# Lumiboard_-_main_board_rev_B.net
KiCad netlist of a schematic drawn in EAGLE
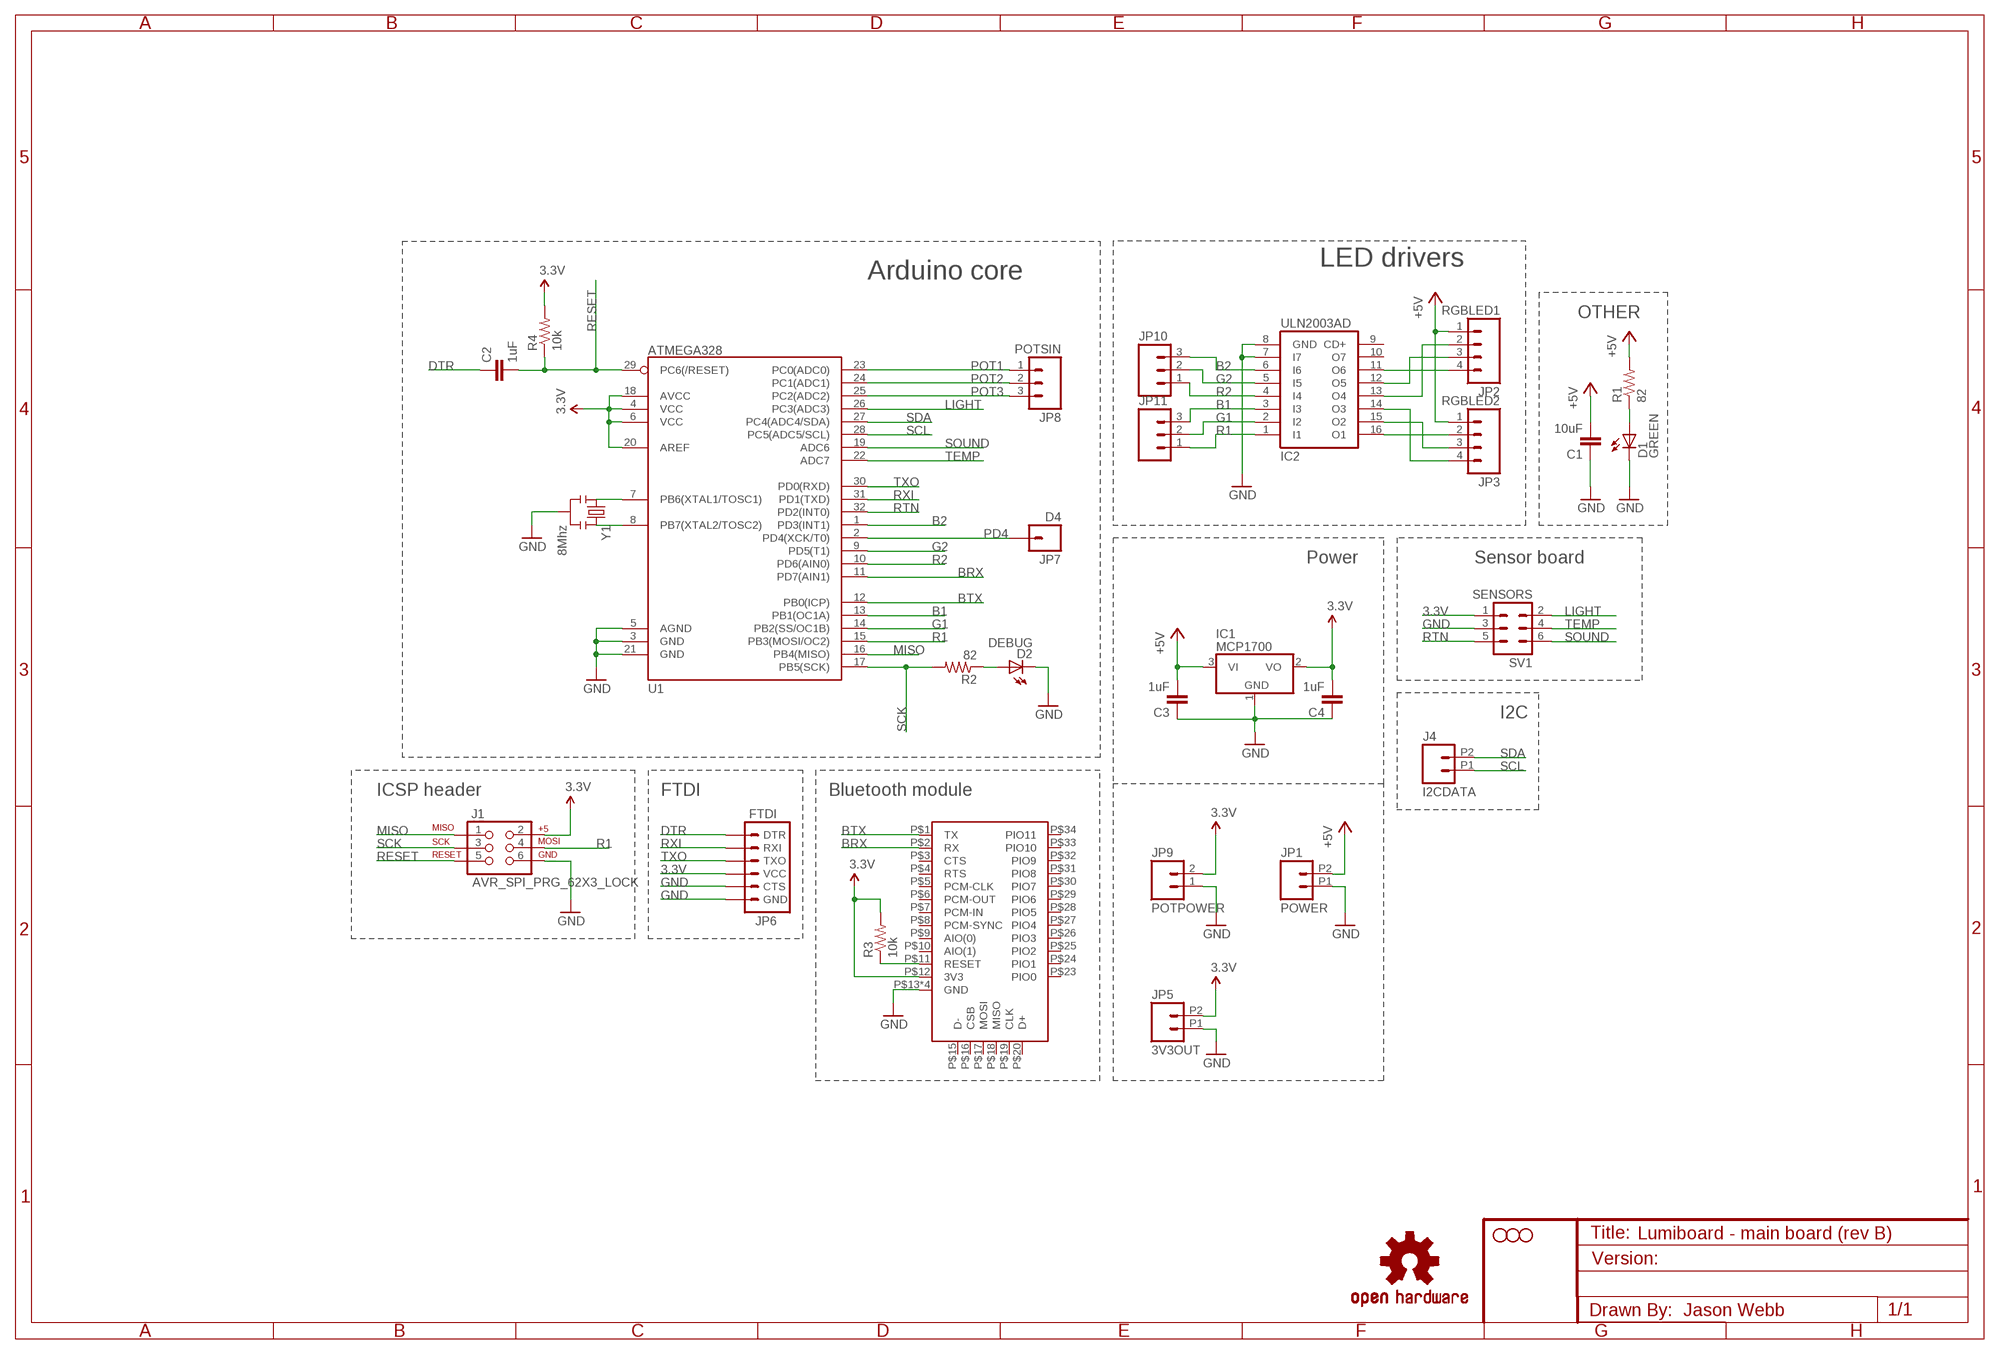
[diagram p0: schematic, sheet 1]

(export (version "E")
  (design (tool "Eeschema 10.0.6"))
  (components
    (comp (ref "C1")
      (value "10uF")
      (footprint "eagle-import:0805")
      (libsource (lib "eagle-import") (part "CAP0805"))
    )
    (comp (ref "C2")
      (value "1uF")
      (footprint "eagle-import:0805")
      (libsource (lib "eagle-import") (part "CAP0805"))
    )
    (comp (ref "C3")
      (value "1uF")
      (footprint "eagle-import:0805")
      (libsource (lib "eagle-import") (part "CAP0805"))
    )
    (comp (ref "C4")
      (value "1uF")
      (footprint "eagle-import:0805")
      (libsource (lib "eagle-import") (part "CAP0805"))
    )
    (comp (ref "D1")
      (value "GREEN")
      (footprint "eagle-import:CHIPLED_0805")
      (libsource (lib "eagle-import") (part "LEDCHIPLED_0805"))
    )
    (comp (ref "D2")
      (value "DEBUG")
      (footprint "eagle-import:CHIPLED_0805")
      (libsource (lib "eagle-import") (part "LEDCHIPLED_0805"))
    )
    (comp (ref "H1")
      (value "STAND-OFFTIGHT")
      (footprint "eagle-import:STAND-OFF-TIGHT")
      (libsource (lib "eagle-import") (part "STAND-OFFTIGHT"))
    )
    (comp (ref "H2")
      (value "STAND-OFFTIGHT")
      (footprint "eagle-import:STAND-OFF-TIGHT")
      (libsource (lib "eagle-import") (part "STAND-OFFTIGHT"))
    )
    (comp (ref "H3")
      (value "STAND-OFFTIGHT")
      (footprint "eagle-import:STAND-OFF-TIGHT")
      (libsource (lib "eagle-import") (part "STAND-OFFTIGHT"))
    )
    (comp (ref "IC1")
      (value "MCP1700")
      (footprint "eagle-import:SOT23")
      (libsource (lib "eagle-import") (part "MCP1703CB"))
    )
    (comp (ref "IC2")
      (value "ULN2003AD")
      (footprint "eagle-import:SO16")
      (libsource (lib "eagle-import") (part "ULN2003AD"))
    )
    (comp (ref "J1")
      (value "AVR_SPI_PRG_62X3_LOCK")
      (footprint "eagle-import:2X3_LOCK")
      (libsource (lib "eagle-import") (part "AVR_SPI_PRG_62X3_LOCK"))
    )
    (comp (ref "J4")
      (value "I2CDATA")
      (footprint "eagle-import:1X02_2.54_SCREWTERM")
      (libsource (lib "eagle-import") (part "M022.54MM_SCREWTERM"))
    )
    (comp (ref "JP1")
      (value "POWER")
      (footprint "eagle-import:1X02_2.54_SCREWTERM")
      (libsource (lib "eagle-import") (part "M022.54MM_SCREWTERM"))
    )
    (comp (ref "JP2")
      (value "RGBLED1")
      (footprint "eagle-import:1X04")
      (libsource (lib "eagle-import") (part "M04PTH"))
    )
    (comp (ref "JP3")
      (value "RGBLED2")
      (footprint "eagle-import:1X04")
      (libsource (lib "eagle-import") (part "M04PTH"))
    )
    (comp (ref "JP5")
      (value "3V3OUT")
      (footprint "eagle-import:1X02_2.54_SCREWTERM")
      (libsource (lib "eagle-import") (part "M022.54MM_SCREWTERM"))
    )
    (comp (ref "JP6")
      (value "FTDI")
      (footprint "eagle-import:1X06_LOCK")
      (libsource (lib "eagle-import") (part "ARDUINO_SERIAL_PROGRAMLOCK"))
    )
    (comp (ref "JP7")
      (value "D4")
      (footprint "eagle-import:1X01")
      (libsource (lib "eagle-import") (part "M01PTH"))
    )
    (comp (ref "JP8")
      (value "POTSIN")
      (footprint "eagle-import:1X03")
      (libsource (lib "eagle-import") (part "M03PTH"))
    )
    (comp (ref "JP9")
      (value "POTPOWER")
      (footprint "eagle-import:1X02")
      (libsource (lib "eagle-import") (part "M02PTH"))
    )
    (comp (ref "JP10")
      (value "M03PTH")
      (footprint "eagle-import:1X03")
      (libsource (lib "eagle-import") (part "SparkFun-Connectors_M03PTH"))
    )
    (comp (ref "JP11")
      (value "M03PTH")
      (footprint "eagle-import:1X03")
      (libsource (lib "eagle-import") (part "SparkFun-Connectors_M03PTH"))
    )
    (comp (ref "LOGO1")
      (value "OSHW-LOGOL")
      (footprint "eagle-import:OSHW-LOGO-L")
      (libsource (lib "eagle-import") (part "OSHW-LOGOL"))
    )
    (comp (ref "R1")
      (value "82")
      (footprint "eagle-import:R0805")
      (libsource (lib "eagle-import") (part "R-US_R0805"))
    )
    (comp (ref "R2")
      (value "82")
      (footprint "eagle-import:R0805")
      (libsource (lib "eagle-import") (part "R-US_R0805"))
    )
    (comp (ref "R3")
      (value "10k")
      (footprint "eagle-import:R0805")
      (libsource (lib "eagle-import") (part "R-US_R0805"))
    )
    (comp (ref "R4")
      (value "10k")
      (footprint "eagle-import:R0805")
      (libsource (lib "eagle-import") (part "R-US_R0805"))
    )
    (comp (ref "SV1")
      (value "SENSORS")
      (footprint "eagle-import:ML6")
      (libsource (lib "eagle-import") (part "ML6"))
    )
    (comp (ref "U1")
      (value "ATMEGA328")
      (footprint "eagle-import:TQFP32-08")
      (libsource (lib "eagle-import") (part "ATMEGA168"))
    )
    (comp (ref "U2")
      (value "DX_BT_MODULE")
      (footprint "eagle-import:DXBLUETOOTHMODULE")
      (libsource (lib "eagle-import") (part "DX_BT_MODULE"))
    )
    (comp (ref "Y1")
      (value "8Mhz")
      (footprint "eagle-import:RESONATOR-SMD")
      (libsource (lib "eagle-import") (part "RESONATORSMD"))
    )
  )
  (nets
    (net (code "1") (name "+5V") (class "Default")
      (node (ref "C1") (pin "2") (pinfunction "2_2") (pintype "passive"))
      (node (ref "C3") (pin "2") (pinfunction "2_2") (pintype "passive"))
      (node (ref "IC1") (pin "3") (pinfunction "VI_3") (pintype "input"))
      (node (ref "JP1") (pin "P2") (pinfunction "2_P2") (pintype "passive"))
      (node (ref "JP2") (pin "1") (pinfunction "1_1") (pintype "passive"))
      (node (ref "JP3") (pin "1") (pinfunction "1_1") (pintype "passive"))
      (node (ref "R1") (pin "2") (pinfunction "2_2") (pintype "passive"))
    )
    (net (code "2") (name "/B1") (class "Default")
      (node (ref "IC2") (pin "3") (pinfunction "I3_3") (pintype "input"))
      (node (ref "JP11") (pin "3") (pinfunction "3_3") (pintype "passive"))
      (node (ref "U1") (pin "13") (pinfunction "PB1(OC1A)_13") (pintype "bidirectional"))
    )
    (net (code "3") (name "/B2") (class "Default")
      (node (ref "IC2") (pin "6") (pinfunction "I6_6") (pintype "input"))
      (node (ref "JP10") (pin "3") (pinfunction "3_3") (pintype "passive"))
      (node (ref "U1") (pin "1") (pinfunction "PD3(INT1)_1") (pintype "bidirectional"))
    )
    (net (code "4") (name "/BRX") (class "Default")
      (node (ref "U1") (pin "11") (pinfunction "PD7(AIN1)_11") (pintype "bidirectional"))
      (node (ref "U2") (pin "P$2") (pinfunction "RX_P$2") (pintype "input"))
    )
    (net (code "5") (name "/BTX") (class "Default")
      (node (ref "U1") (pin "12") (pinfunction "PB0(ICP)_12") (pintype "bidirectional"))
      (node (ref "U2") (pin "P$1") (pinfunction "TX_P$1") (pintype "output"))
    )
    (net (code "6") (name "/DTR") (class "Default")
      (node (ref "C2") (pin "1") (pinfunction "1_1") (pintype "passive"))
      (node (ref "JP6") (pin "1") (pinfunction "DTR_1") (pintype "passive"))
    )
    (net (code "7") (name "/G1") (class "Default")
      (node (ref "IC2") (pin "2") (pinfunction "I2_2") (pintype "input"))
      (node (ref "JP11") (pin "2") (pinfunction "2_2") (pintype "passive"))
      (node (ref "U1") (pin "14") (pinfunction "PB2(SS/OC1B)_14") (pintype "bidirectional"))
    )
    (net (code "8") (name "/G2") (class "Default")
      (node (ref "IC2") (pin "5") (pinfunction "I5_5") (pintype "input"))
      (node (ref "JP10") (pin "2") (pinfunction "2_2") (pintype "passive"))
      (node (ref "U1") (pin "9") (pinfunction "PD5(T1)_9") (pintype "bidirectional"))
    )
    (net (code "9") (name "/LIGHT") (class "Default")
      (node (ref "SV1") (pin "2") (pinfunction "2_2") (pintype "passive"))
      (node (ref "U1") (pin "26") (pinfunction "PC3(ADC3)_26") (pintype "bidirectional"))
    )
    (net (code "10") (name "/MISO") (class "Default")
      (node (ref "J1") (pin "1") (pinfunction "1_1") (pintype "passive"))
      (node (ref "U1") (pin "16") (pinfunction "PB4(MISO)_16") (pintype "bidirectional"))
    )
    (net (code "11") (name "/PD4") (class "Default")
      (node (ref "JP7") (pin "1") (pinfunction "1_1") (pintype "passive"))
      (node (ref "U1") (pin "2") (pinfunction "PD4(XCK/T0)_2") (pintype "bidirectional"))
    )
    (net (code "12") (name "/POT1") (class "Default")
      (node (ref "JP8") (pin "1") (pinfunction "1_1") (pintype "passive"))
      (node (ref "U1") (pin "23") (pinfunction "PC0(ADC0)_23") (pintype "bidirectional"))
    )
    (net (code "13") (name "/POT2") (class "Default")
      (node (ref "JP8") (pin "2") (pinfunction "2_2") (pintype "passive"))
      (node (ref "U1") (pin "24") (pinfunction "PC1(ADC1)_24") (pintype "bidirectional"))
    )
    (net (code "14") (name "/POT3") (class "Default")
      (node (ref "JP8") (pin "3") (pinfunction "3_3") (pintype "passive"))
      (node (ref "U1") (pin "25") (pinfunction "PC2(ADC2)_25") (pintype "bidirectional"))
    )
    (net (code "15") (name "/R1") (class "Default")
      (node (ref "IC2") (pin "1") (pinfunction "I1_1") (pintype "input"))
      (node (ref "J1") (pin "4") (pinfunction "4_4") (pintype "passive"))
      (node (ref "JP11") (pin "1") (pinfunction "1_1") (pintype "passive"))
      (node (ref "U1") (pin "15") (pinfunction "PB3(MOSI/OC2)_15") (pintype "bidirectional"))
    )
    (net (code "16") (name "/R2") (class "Default")
      (node (ref "IC2") (pin "4") (pinfunction "I4_4") (pintype "input"))
      (node (ref "JP10") (pin "1") (pinfunction "1_1") (pintype "passive"))
      (node (ref "U1") (pin "10") (pinfunction "PD6(AIN0)_10") (pintype "bidirectional"))
    )
    (net (code "17") (name "/RESET") (class "Default")
      (node (ref "C2") (pin "2") (pinfunction "2_2") (pintype "passive"))
      (node (ref "J1") (pin "5") (pinfunction "5_5") (pintype "passive"))
      (node (ref "R4") (pin "1") (pinfunction "1_1") (pintype "passive"))
      (node (ref "U1") (pin "29") (pinfunction "PC6(/RESET)_29") (pintype "bidirectional"))
    )
    (net (code "18") (name "/RTN") (class "Default")
      (node (ref "SV1") (pin "5") (pinfunction "5_5") (pintype "passive"))
      (node (ref "U1") (pin "32") (pinfunction "PD2(INT0)_32") (pintype "bidirectional"))
    )
    (net (code "19") (name "/RXI") (class "Default")
      (node (ref "JP6") (pin "2") (pinfunction "RXI_2") (pintype "passive"))
      (node (ref "U1") (pin "31") (pinfunction "PD1(TXD)_31") (pintype "bidirectional"))
    )
    (net (code "20") (name "/SCK") (class "Default")
      (node (ref "J1") (pin "3") (pinfunction "3_3") (pintype "passive"))
      (node (ref "R2") (pin "2") (pinfunction "2_2") (pintype "passive"))
      (node (ref "U1") (pin "17") (pinfunction "PB5(SCK)_17") (pintype "bidirectional"))
    )
    (net (code "21") (name "/SCL") (class "Default")
      (node (ref "J4") (pin "P1") (pinfunction "1_P1") (pintype "passive"))
      (node (ref "U1") (pin "28") (pinfunction "PC5(ADC5/SCL)_28") (pintype "bidirectional"))
    )
    (net (code "22") (name "/SDA") (class "Default")
      (node (ref "J4") (pin "P2") (pinfunction "2_P2") (pintype "passive"))
      (node (ref "U1") (pin "27") (pinfunction "PC4(ADC4/SDA)_27") (pintype "bidirectional"))
    )
    (net (code "23") (name "/SOUND") (class "Default")
      (node (ref "SV1") (pin "6") (pinfunction "6_6") (pintype "passive"))
      (node (ref "U1") (pin "19") (pinfunction "ADC6_19") (pintype "bidirectional"))
    )
    (net (code "24") (name "/TEMP") (class "Default")
      (node (ref "SV1") (pin "4") (pinfunction "4_4") (pintype "passive"))
      (node (ref "U1") (pin "22") (pinfunction "ADC7_22") (pintype "bidirectional"))
    )
    (net (code "25") (name "/TXO") (class "Default")
      (node (ref "JP6") (pin "3") (pinfunction "TXO_3") (pintype "passive"))
      (node (ref "U1") (pin "30") (pinfunction "PD0(RXD)_30") (pintype "bidirectional"))
    )
    (net (code "26") (name "3.3V") (class "Default")
      (node (ref "C4") (pin "2") (pinfunction "2_2") (pintype "passive"))
      (node (ref "IC1") (pin "2") (pinfunction "VO_2") (pintype "passive"))
      (node (ref "J1") (pin "2") (pinfunction "2_2") (pintype "passive"))
      (node (ref "JP5") (pin "P2") (pinfunction "2_P2") (pintype "passive"))
      (node (ref "JP6") (pin "4") (pinfunction "VCC_4") (pintype "passive"))
      (node (ref "JP9") (pin "2") (pinfunction "2_2") (pintype "passive"))
      (node (ref "R3") (pin "2") (pinfunction "2_2") (pintype "passive"))
      (node (ref "R4") (pin "2") (pinfunction "2_2") (pintype "passive"))
      (node (ref "SV1") (pin "1") (pinfunction "1_1") (pintype "passive"))
      (node (ref "U1") (pin "18") (pinfunction "AVCC_18") (pintype "bidirectional"))
      (node (ref "U1") (pin "20") (pinfunction "AREF_20") (pintype "bidirectional"))
      (node (ref "U1") (pin "4") (pinfunction "VCC_4") (pintype "bidirectional"))
      (node (ref "U1") (pin "6") (pinfunction "VCC_6") (pintype "bidirectional"))
      (node (ref "U2") (pin "P$12") (pinfunction "3V3_P$12") (pintype "power_in"))
    )
    (net (code "27") (name "GND") (class "Default")
      (node (ref "C1") (pin "1") (pinfunction "1_1") (pintype "passive"))
      (node (ref "C3") (pin "1") (pinfunction "1_1") (pintype "passive"))
      (node (ref "C4") (pin "1") (pinfunction "1_1") (pintype "passive"))
      (node (ref "D1") (pin "C") (pinfunction "C_C") (pintype "passive"))
      (node (ref "D2") (pin "C") (pinfunction "C_C") (pintype "passive"))
      (node (ref "IC1") (pin "1") (pinfunction "GND_1") (pintype "passive"))
      (node (ref "IC2") (pin "7") (pinfunction "I7_7") (pintype "input"))
      (node (ref "IC2") (pin "8") (pinfunction "GND_8") (pintype "power_in"))
      (node (ref "J1") (pin "6") (pinfunction "6_6") (pintype "passive"))
      (node (ref "JP1") (pin "P1") (pinfunction "1_P1") (pintype "passive"))
      (node (ref "JP5") (pin "P1") (pinfunction "1_P1") (pintype "passive"))
      (node (ref "JP6") (pin "5") (pinfunction "CTS_5") (pintype "passive"))
      (node (ref "JP6") (pin "6") (pinfunction "GND_6") (pintype "passive"))
      (node (ref "JP9") (pin "1") (pinfunction "1_1") (pintype "passive"))
      (node (ref "SV1") (pin "3") (pinfunction "3_3") (pintype "passive"))
      (node (ref "U1") (pin "21") (pinfunction "GND_21") (pintype "bidirectional"))
      (node (ref "U1") (pin "3") (pinfunction "GND_3") (pintype "bidirectional"))
      (node (ref "U1") (pin "5") (pinfunction "AGND_5") (pintype "bidirectional"))
      (node (ref "U2") (pin "P$13") (pinfunction "GND_P$13") (pintype "power_in"))
      (node (ref "U2") (pin "P$14") (pinfunction "GND_P$14") (pintype "power_in"))
      (node (ref "U2") (pin "P$21") (pinfunction "GND_P$21") (pintype "power_in"))
      (node (ref "U2") (pin "P$22") (pinfunction "GND_P$22") (pintype "power_in"))
      (node (ref "Y1") (pin "2") (pinfunction "2_2") (pintype "passive"))
    )
    (net (code "28") (name "Net-(D1-PadA)") (class "Default")
      (node (ref "D1") (pin "A") (pinfunction "A_A") (pintype "passive"))
      (node (ref "R1") (pin "1") (pinfunction "1_1") (pintype "passive"))
    )
    (net (code "29") (name "Net-(D2-PadA)") (class "Default")
      (node (ref "D2") (pin "A") (pinfunction "A_A") (pintype "passive"))
      (node (ref "R2") (pin "1") (pinfunction "1_1") (pintype "passive"))
    )
    (net (code "30") (name "Net-(IC2-O1)") (class "Default")
      (node (ref "IC2") (pin "16") (pinfunction "O1_16") (pintype "open_collector"))
      (node (ref "JP3") (pin "2") (pinfunction "2_2") (pintype "passive"))
    )
    (net (code "31") (name "Net-(IC2-O2)") (class "Default")
      (node (ref "IC2") (pin "15") (pinfunction "O2_15") (pintype "open_collector"))
      (node (ref "JP3") (pin "3") (pinfunction "3_3") (pintype "passive"))
    )
    (net (code "32") (name "Net-(IC2-O3)") (class "Default")
      (node (ref "IC2") (pin "14") (pinfunction "O3_14") (pintype "open_collector"))
      (node (ref "JP3") (pin "4") (pinfunction "4_4") (pintype "passive"))
    )
    (net (code "33") (name "Net-(IC2-O4)") (class "Default")
      (node (ref "IC2") (pin "13") (pinfunction "O4_13") (pintype "open_collector"))
      (node (ref "JP2") (pin "2") (pinfunction "2_2") (pintype "passive"))
    )
    (net (code "34") (name "Net-(IC2-O5)") (class "Default")
      (node (ref "IC2") (pin "12") (pinfunction "O5_12") (pintype "open_collector"))
      (node (ref "JP2") (pin "3") (pinfunction "3_3") (pintype "passive"))
    )
    (net (code "35") (name "Net-(IC2-O6)") (class "Default")
      (node (ref "IC2") (pin "11") (pinfunction "O6_11") (pintype "open_collector"))
      (node (ref "JP2") (pin "4") (pinfunction "4_4") (pintype "passive"))
    )
    (net (code "36") (name "Net-(U1-PB6(XTAL1{slash}TOSC1))") (class "Default")
      (node (ref "U1") (pin "7") (pinfunction "PB6(XTAL1/TOSC1)_7") (pintype "bidirectional"))
      (node (ref "Y1") (pin "1") (pinfunction "1_1") (pintype "passive"))
    )
    (net (code "37") (name "Net-(U1-PB7(XTAL2{slash}TOSC2))") (class "Default")
      (node (ref "U1") (pin "8") (pinfunction "PB7(XTAL2/TOSC2)_8") (pintype "bidirectional"))
      (node (ref "Y1") (pin "3") (pinfunction "3_3") (pintype "passive"))
    )
    (net (code "38") (name "Net-(U2-RESET)") (class "Default")
      (node (ref "R3") (pin "1") (pinfunction "1_1") (pintype "passive"))
      (node (ref "U2") (pin "P$11") (pinfunction "RESET_P$11") (pintype "input"))
    )
    (net (code "39") (name "unconnected-(IC2-CD+-Pad9)") (class "Default")
      (node (ref "IC2") (pin "9") (pinfunction "CD+_9") (pintype "passive"))
    )
    (net (code "40") (name "unconnected-(IC2-O7-Pad10)") (class "Default")
      (node (ref "IC2") (pin "10") (pinfunction "O7_10") (pintype "open_collector"))
    )
    (net (code "41") (name "unconnected-(U2-AIO(0)-PadP$9)") (class "Default")
      (node (ref "U2") (pin "P$9") (pinfunction "AIO(0)_P$9") (pintype "bidirectional"))
    )
    (net (code "42") (name "unconnected-(U2-AIO(1)-PadP$10)") (class "Default")
      (node (ref "U2") (pin "P$10") (pinfunction "AIO(1)_P$10") (pintype "bidirectional"))
    )
    (net (code "43") (name "unconnected-(U2-CLK-PadP$19)") (class "Default")
      (node (ref "U2") (pin "P$19") (pinfunction "CLK_P$19") (pintype "input"))
    )
    (net (code "44") (name "unconnected-(U2-CSB-PadP$16)") (class "Default")
      (node (ref "U2") (pin "P$16") (pinfunction "CSB_P$16") (pintype "input"))
    )
    (net (code "45") (name "unconnected-(U2-CTS-PadP$3)") (class "Default")
      (node (ref "U2") (pin "P$3") (pinfunction "CTS_P$3") (pintype "input"))
    )
    (net (code "46") (name "unconnected-(U2-D+-PadP$20)") (class "Default")
      (node (ref "U2") (pin "P$20") (pinfunction "D+_P$20") (pintype "bidirectional"))
    )
    (net (code "47") (name "unconnected-(U2-D--PadP$15)") (class "Default")
      (node (ref "U2") (pin "P$15") (pinfunction "D-_P$15") (pintype "bidirectional"))
    )
    (net (code "48") (name "unconnected-(U2-MISO-PadP$18)") (class "Default")
      (node (ref "U2") (pin "P$18") (pinfunction "MISO_P$18") (pintype "output"))
    )
    (net (code "49") (name "unconnected-(U2-MOSI-PadP$17)") (class "Default")
      (node (ref "U2") (pin "P$17") (pinfunction "MOSI_P$17") (pintype "input"))
    )
    (net (code "50") (name "unconnected-(U2-PCM-CLK-PadP$5)") (class "Default")
      (node (ref "U2") (pin "P$5") (pinfunction "PCM-CLK_P$5") (pintype "bidirectional"))
    )
    (net (code "51") (name "unconnected-(U2-PCM-IN-PadP$7)") (class "Default")
      (node (ref "U2") (pin "P$7") (pinfunction "PCM-IN_P$7") (pintype "input"))
    )
    (net (code "52") (name "unconnected-(U2-PCM-OUT-PadP$6)") (class "Default")
      (node (ref "U2") (pin "P$6") (pinfunction "PCM-OUT_P$6") (pintype "output"))
    )
    (net (code "53") (name "unconnected-(U2-PCM-SYNC-PadP$8)") (class "Default")
      (node (ref "U2") (pin "P$8") (pinfunction "PCM-SYNC_P$8") (pintype "bidirectional"))
    )
    (net (code "54") (name "unconnected-(U2-PIO0-PadP$23)") (class "Default")
      (node (ref "U2") (pin "P$23") (pinfunction "PIO0_P$23") (pintype "bidirectional"))
    )
    (net (code "55") (name "unconnected-(U2-PIO1-PadP$24)") (class "Default")
      (node (ref "U2") (pin "P$24") (pinfunction "PIO1_P$24") (pintype "bidirectional"))
    )
    (net (code "56") (name "unconnected-(U2-PIO2-PadP$25)") (class "Default")
      (node (ref "U2") (pin "P$25") (pinfunction "PIO2_P$25") (pintype "bidirectional"))
    )
    (net (code "57") (name "unconnected-(U2-PIO3-PadP$26)") (class "Default")
      (node (ref "U2") (pin "P$26") (pinfunction "PIO3_P$26") (pintype "bidirectional"))
    )
    (net (code "58") (name "unconnected-(U2-PIO4-PadP$27)") (class "Default")
      (node (ref "U2") (pin "P$27") (pinfunction "PIO4_P$27") (pintype "bidirectional"))
    )
    (net (code "59") (name "unconnected-(U2-PIO5-PadP$28)") (class "Default")
      (node (ref "U2") (pin "P$28") (pinfunction "PIO5_P$28") (pintype "bidirectional"))
    )
    (net (code "60") (name "unconnected-(U2-PIO6-PadP$29)") (class "Default")
      (node (ref "U2") (pin "P$29") (pinfunction "PIO6_P$29") (pintype "bidirectional"))
    )
    (net (code "61") (name "unconnected-(U2-PIO7-PadP$30)") (class "Default")
      (node (ref "U2") (pin "P$30") (pinfunction "PIO7_P$30") (pintype "bidirectional"))
    )
    (net (code "62") (name "unconnected-(U2-PIO8-PadP$31)") (class "Default")
      (node (ref "U2") (pin "P$31") (pinfunction "PIO8_P$31") (pintype "bidirectional"))
    )
    (net (code "63") (name "unconnected-(U2-PIO9-PadP$32)") (class "Default")
      (node (ref "U2") (pin "P$32") (pinfunction "PIO9_P$32") (pintype "bidirectional"))
    )
    (net (code "64") (name "unconnected-(U2-PIO10-PadP$33)") (class "Default")
      (node (ref "U2") (pin "P$33") (pinfunction "PIO10_P$33") (pintype "bidirectional"))
    )
    (net (code "65") (name "unconnected-(U2-PIO11-PadP$34)") (class "Default")
      (node (ref "U2") (pin "P$34") (pinfunction "PIO11_P$34") (pintype "bidirectional"))
    )
    (net (code "66") (name "unconnected-(U2-RTS-PadP$4)") (class "Default")
      (node (ref "U2") (pin "P$4") (pinfunction "RTS_P$4") (pintype "output"))
    )
  )
)
